# MB_ADC.net
KiCad netlist of a schematic drawn in Altium Designer
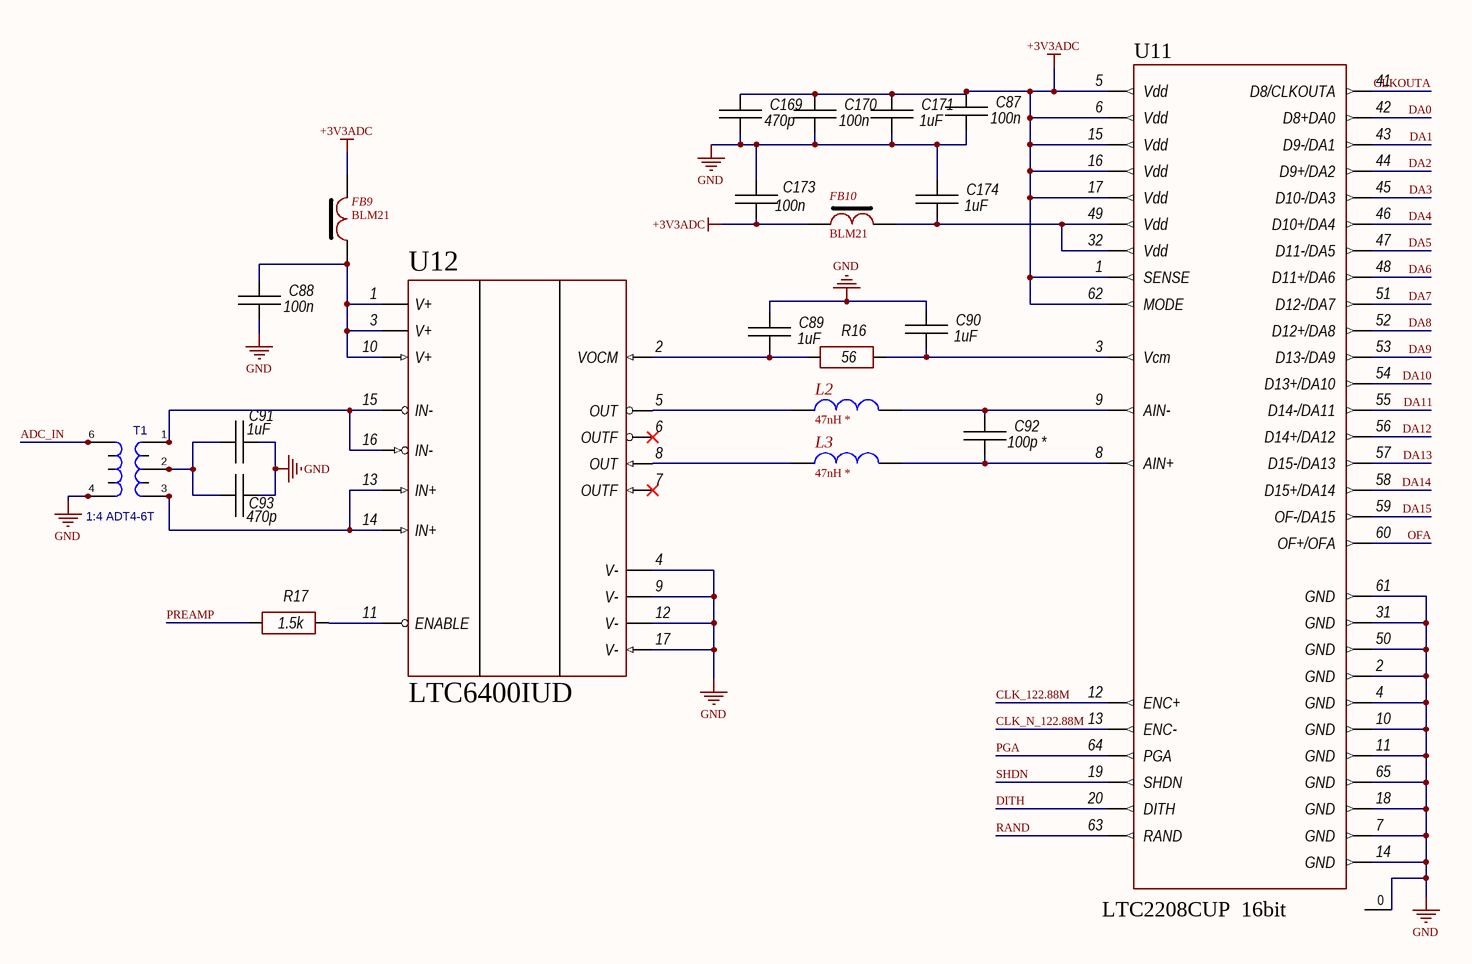
[diagram p0: MB_ADC.SchDoc]

(export (version "E")
  (design (tool "Eeschema 10.0.6"))
  (components
    (comp (ref "C87")
      (value "100n")
      (footprint "standard:CH0805C")
      (libsource (lib "Discrete") (part "Capacitor"))
    )
    (comp (ref "C88")
      (value "100n")
      (footprint "standard:CH0805C")
      (libsource (lib "Discrete") (part "Capacitor"))
    )
    (comp (ref "C89")
      (value "1uF")
      (footprint "standard:CH0805C")
      (libsource (lib "Discrete") (part "Capacitor"))
    )
    (comp (ref "C90")
      (value "1uF")
      (footprint "standard:CH0805C")
      (libsource (lib "Discrete") (part "Capacitor"))
    )
    (comp (ref "C91")
      (value "1uF")
      (footprint "standard:CH0805C")
      (libsource (lib "Discrete") (part "Capacitor"))
    )
    (comp (ref "C92")
      (value "100p *")
      (footprint "standard:CH0805C")
      (libsource (lib "") (part "Capacitor_1"))
    )
    (comp (ref "C93")
      (value "470p")
      (footprint "standard:CH0805C")
      (libsource (lib "Discrete") (part "Capacitor"))
    )
    (comp (ref "C169")
      (value "470p")
      (footprint "standard:CH0805C")
      (libsource (lib "Discrete") (part "Capacitor"))
    )
    (comp (ref "C170")
      (value "100n")
      (footprint "standard:CH0805C")
      (libsource (lib "Discrete") (part "Capacitor"))
    )
    (comp (ref "C171")
      (value "1uF")
      (footprint "standard:CH0805C")
      (libsource (lib "Discrete") (part "Capacitor"))
    )
    (comp (ref "C173")
      (value "100n")
      (footprint "standard:CH0805C")
      (libsource (lib "Discrete") (part "Capacitor"))
    )
    (comp (ref "C174")
      (value "1uF")
      (footprint "standard:CH0805C")
      (libsource (lib "Discrete") (part "Capacitor"))
    )
    (comp (ref "FB9") (value "BLM21") (footprint "CH0805L") (libsource (lib "Discrete") (part "FB-1")))
    (comp (ref "FB10") (value "BLM21") (footprint "CH0805F") (libsource (lib "Discrete") (part "FB-1")))
    (comp (ref "L2") (value "47nH *") (footprint "CH1210L") (libsource (lib "Discrete") (part "Inductor-2")))
    (comp (ref "L3") (value "47nH *") (footprint "CH1210L") (libsource (lib "Discrete") (part "Inductor-2")))
    (comp (ref "R16")
      (value "56")
      (footprint "standard:CH0805R")
      (libsource (lib "Discrete") (part "Resistor"))
    )
    (comp (ref "R17")
      (value "1.5k")
      (footprint "standard:CH0805R")
      (libsource (lib "Discrete") (part "Resistor"))
    )
    (comp (ref "T1")
      (value "1:4 ADT4-6T")
      (footprint "TRANSF_ACORE2")
      (description "Transformer")
      (libsource (lib "MOTHERBOARD_1") (part "TRANSF_ACORE2"))
    )
    (comp (ref "U11")
      (value "LTC2208CUP  16bit")
      (footprint "64-QFN (9x9)")
      (libsource (lib "Digital") (part "LTC2208CUP"))
    )
    (comp (ref "U12")
      (value "LTC6400IUD")
      (footprint "16-QFN 3x3")
      (libsource (lib "Digital") (part "LTC6400IUD"))
    )
  )
  (nets
    (net (code "1") (name "+3V3ADC") (class "Default")
      (node (ref "C169") (pin "1") (pinfunction "1_1") (pintype "power_in"))
      (node (ref "C170") (pin "1") (pinfunction "1_1") (pintype "power_in"))
      (node (ref "C171") (pin "1") (pinfunction "1_1") (pintype "power_in"))
      (node (ref "C173") (pin "2") (pinfunction "2_2") (pintype "power_in"))
      (node (ref "C87") (pin "1") (pinfunction "1_1") (pintype "power_in"))
      (node (ref "FB10") (pin "2") (pinfunction "2_2") (pintype "passive"))
      (node (ref "FB9") (pin "1") (pinfunction "1_1") (pintype "passive"))
      (node (ref "U11") (pin "1") (pinfunction "SENSE_1") (pintype "output"))
      (node (ref "U11") (pin "15") (pinfunction "Vdd_15") (pintype "output"))
      (node (ref "U11") (pin "16") (pinfunction "Vdd_16") (pintype "output"))
      (node (ref "U11") (pin "17") (pinfunction "Vdd_17") (pintype "output"))
      (node (ref "U11") (pin "5") (pinfunction "Vdd_5") (pintype "output"))
      (node (ref "U11") (pin "6") (pinfunction "Vdd_6") (pintype "output"))
      (node (ref "U11") (pin "62") (pinfunction "MODE_62") (pintype "output"))
    )
    (net (code "2") (name "/ADC_IN") (class "Default")
      (node (ref "T1") (pin "10") (pinfunction "0_10") (pintype "passive"))
      (node (ref "T1") (pin "6") (pinfunction "P2_6") (pintype "passive"))
    )
    (net (code "3") (name "/CLKOUTA") (class "Default")
      (node (ref "U11") (pin "41") (pinfunction "D8/CLKOUTA_41") (pintype "output"))
    )
    (net (code "4") (name "/CLK_122.88M") (class "Default")
      (node (ref "U11") (pin "12") (pinfunction "ENC+_12") (pintype "output"))
    )
    (net (code "5") (name "/CLK_N_122.88M") (class "Default")
      (node (ref "U11") (pin "13") (pinfunction "ENC-_13") (pintype "output"))
    )
    (net (code "6") (name "/DA0") (class "Default")
      (node (ref "U11") (pin "42") (pinfunction "D8+DA0_42") (pintype "output"))
    )
    (net (code "7") (name "/DA1") (class "Default")
      (node (ref "U11") (pin "43") (pinfunction "D9-/DA1_43") (pintype "output"))
    )
    (net (code "8") (name "/DA2") (class "Default")
      (node (ref "U11") (pin "44") (pinfunction "D9+/DA2_44") (pintype "output"))
    )
    (net (code "9") (name "/DA3") (class "Default")
      (node (ref "U11") (pin "45") (pinfunction "D10-/DA3_45") (pintype "output"))
    )
    (net (code "10") (name "/DA4") (class "Default")
      (node (ref "U11") (pin "46") (pinfunction "D10+/DA4_46") (pintype "output"))
    )
    (net (code "11") (name "/DA5") (class "Default")
      (node (ref "U11") (pin "47") (pinfunction "D11-/DA5_47") (pintype "output"))
    )
    (net (code "12") (name "/DA6") (class "Default")
      (node (ref "U11") (pin "48") (pinfunction "D11+/DA6_48") (pintype "output"))
    )
    (net (code "13") (name "/DA7") (class "Default")
      (node (ref "U11") (pin "51") (pinfunction "D12-/DA7_51") (pintype "output"))
    )
    (net (code "14") (name "/DA8") (class "Default")
      (node (ref "U11") (pin "52") (pinfunction "D12+/DA8_52") (pintype "output"))
    )
    (net (code "15") (name "/DA9") (class "Default")
      (node (ref "U11") (pin "53") (pinfunction "D13-/DA9_53") (pintype "output"))
    )
    (net (code "16") (name "/DA10") (class "Default")
      (node (ref "U11") (pin "54") (pinfunction "D13+/DA10_54") (pintype "output"))
    )
    (net (code "17") (name "/DA11") (class "Default")
      (node (ref "U11") (pin "55") (pinfunction "D14-/DA11_55") (pintype "output"))
    )
    (net (code "18") (name "/DA12") (class "Default")
      (node (ref "U11") (pin "56") (pinfunction "D14+/DA12_56") (pintype "output"))
    )
    (net (code "19") (name "/DA13") (class "Default")
      (node (ref "U11") (pin "57") (pinfunction "D15-/DA13_57") (pintype "output"))
    )
    (net (code "20") (name "/DA14") (class "Default")
      (node (ref "U11") (pin "58") (pinfunction "D15+/DA14_58") (pintype "output"))
    )
    (net (code "21") (name "/DA15") (class "Default")
      (node (ref "U11") (pin "59") (pinfunction "OF-/DA15_59") (pintype "output"))
    )
    (net (code "22") (name "/DITH") (class "Default")
      (node (ref "U11") (pin "20") (pinfunction "DITH_20") (pintype "output"))
    )
    (net (code "23") (name "/OFA") (class "Default")
      (node (ref "U11") (pin "60") (pinfunction "OF+/OFA_60") (pintype "output"))
    )
    (net (code "24") (name "/PGA") (class "Default")
      (node (ref "U11") (pin "64") (pinfunction "PGA_64") (pintype "output"))
    )
    (net (code "25") (name "/PREAMP") (class "Default")
      (node (ref "R17") (pin "2") (pinfunction "2_2") (pintype "passive"))
    )
    (net (code "26") (name "/RAND") (class "Default")
      (node (ref "U11") (pin "63") (pinfunction "RAND_63") (pintype "output"))
    )
    (net (code "27") (name "/SHDN") (class "Default")
      (node (ref "U11") (pin "19") (pinfunction "SHDN_19") (pintype "output"))
    )
    (net (code "28") (name "GND") (class "Default")
      (node (ref "C169") (pin "2") (pinfunction "2_2") (pintype "power_in"))
      (node (ref "C170") (pin "2") (pinfunction "2_2") (pintype "power_in"))
      (node (ref "C171") (pin "2") (pinfunction "2_2") (pintype "power_in"))
      (node (ref "C173") (pin "1") (pinfunction "1_1") (pintype "power_in"))
      (node (ref "C174") (pin "1") (pinfunction "1_1") (pintype "power_in"))
      (node (ref "C87") (pin "2") (pinfunction "2_2") (pintype "power_in"))
      (node (ref "C88") (pin "2") (pinfunction "2_2") (pintype "power_in"))
      (node (ref "C89") (pin "1") (pinfunction "1_1") (pintype "power_in"))
      (node (ref "C90") (pin "1") (pinfunction "1_1") (pintype "power_in"))
      (node (ref "C91") (pin "2") (pinfunction "2_2") (pintype "power_in"))
      (node (ref "C93") (pin "2") (pinfunction "2_2") (pintype "power_in"))
      (node (ref "T1") (pin "11") (pinfunction "0_11") (pintype "passive"))
      (node (ref "T1") (pin "4") (pinfunction "P1_4") (pintype "passive"))
      (node (ref "U11") (pin "0") (pintype "passive"))
      (node (ref "U11") (pin "10") (pinfunction "GND_10") (pintype "output"))
      (node (ref "U11") (pin "11") (pinfunction "GND_11") (pintype "output"))
      (node (ref "U11") (pin "14") (pinfunction "GND_14") (pintype "output"))
      (node (ref "U11") (pin "18") (pinfunction "GND_18") (pintype "output"))
      (node (ref "U11") (pin "2") (pinfunction "GND_2") (pintype "output"))
      (node (ref "U11") (pin "31") (pinfunction "GND_31") (pintype "output"))
      (node (ref "U11") (pin "4") (pinfunction "GND_4") (pintype "output"))
      (node (ref "U11") (pin "50") (pinfunction "GND_50") (pintype "output"))
      (node (ref "U11") (pin "61") (pinfunction "GND_61") (pintype "output"))
      (node (ref "U11") (pin "65") (pinfunction "GND_65") (pintype "output"))
      (node (ref "U11") (pin "7") (pinfunction "GND_7") (pintype "output"))
      (node (ref "U12") (pin "12") (pinfunction "V-_12") (pintype "power_in"))
      (node (ref "U12") (pin "17") (pinfunction "V-_17") (pintype "input"))
      (node (ref "U12") (pin "4") (pinfunction "V-_4") (pintype "passive"))
      (node (ref "U12") (pin "9") (pinfunction "V-_9") (pintype "power_in"))
    )
    (net (code "29") (name "Net-(C88-Pad1)") (class "Default")
      (node (ref "C88") (pin "1") (pinfunction "1_1") (pintype "power_in"))
      (node (ref "FB9") (pin "2") (pinfunction "2_2") (pintype "passive"))
      (node (ref "U12") (pin "1") (pinfunction "V+_1") (pintype "passive"))
      (node (ref "U12") (pin "10") (pinfunction "V+_10") (pintype "input"))
      (node (ref "U12") (pin "3") (pinfunction "V+_3") (pintype "power_in"))
    )
    (net (code "30") (name "Net-(C174-Pad2)") (class "Default")
      (node (ref "C174") (pin "2") (pinfunction "2_2") (pintype "power_in"))
      (node (ref "FB10") (pin "1") (pinfunction "1_1") (pintype "passive"))
      (node (ref "U11") (pin "32") (pinfunction "Vdd_32") (pintype "output"))
      (node (ref "U11") (pin "49") (pinfunction "Vdd_49") (pintype "output"))
    )
    (net (code "31") (name "Net-(L2-Pad2)") (class "Default")
      (node (ref "L2") (pin "2") (pinfunction "2_2") (pintype "passive"))
      (node (ref "U12") (pin "5") (pinfunction "OUT_5") (pintype "passive"))
    )
    (net (code "32") (name "Net-(L3-Pad2)") (class "Default")
      (node (ref "L3") (pin "2") (pinfunction "2_2") (pintype "passive"))
      (node (ref "U12") (pin "8") (pinfunction "OUT_8") (pintype "input"))
    )
    (net (code "33") (name "Net-(T1-S1)") (class "Default")
      (node (ref "T1") (pin "3") (pinfunction "S1_3") (pintype "passive"))
      (node (ref "T1") (pin "9") (pinfunction "0_9") (pintype "passive"))
      (node (ref "U12") (pin "13") (pinfunction "IN+_13") (pintype "input"))
      (node (ref "U12") (pin "14") (pinfunction "IN+_14") (pintype "input"))
    )
    (net (code "34") (name "Net-(T1-S2)") (class "Default")
      (node (ref "C91") (pin "1") (pinfunction "1_1") (pintype "power_in"))
      (node (ref "C93") (pin "1") (pinfunction "1_1") (pintype "power_in"))
      (node (ref "T1") (pin "2") (pinfunction "S2_2") (pintype "passive"))
      (node (ref "T1") (pin "8") (pinfunction "0_8") (pintype "passive"))
    )
    (net (code "35") (name "Net-(T1-S3)") (class "Default")
      (node (ref "T1") (pin "1") (pinfunction "S3_1") (pintype "passive"))
      (node (ref "T1") (pin "7") (pinfunction "0_7") (pintype "passive"))
      (node (ref "U12") (pin "15") (pinfunction "IN-_15") (pintype "passive"))
      (node (ref "U12") (pin "16") (pinfunction "IN-_16") (pintype "input"))
    )
    (net (code "36") (name "Net-(U11-AIN+)") (class "Default")
      (node (ref "C92") (pin "2") (pinfunction "2_2") (pintype "power_in"))
      (node (ref "L3") (pin "1") (pinfunction "1_1") (pintype "passive"))
      (node (ref "U11") (pin "8") (pinfunction "AIN+_8") (pintype "output"))
    )
    (net (code "37") (name "Net-(U11-AIN-)") (class "Default")
      (node (ref "C92") (pin "1") (pinfunction "1_1") (pintype "power_in"))
      (node (ref "L2") (pin "1") (pinfunction "1_1") (pintype "passive"))
      (node (ref "U11") (pin "9") (pinfunction "AIN-_9") (pintype "output"))
    )
    (net (code "38") (name "Net-(U11-Vcm)") (class "Default")
      (node (ref "C90") (pin "2") (pinfunction "2_2") (pintype "power_in"))
      (node (ref "R16") (pin "1") (pinfunction "1_1") (pintype "passive"))
      (node (ref "U11") (pin "3") (pinfunction "Vcm_3") (pintype "output"))
    )
    (net (code "39") (name "Net-(U12-ENABLE)") (class "Default")
      (node (ref "R17") (pin "1") (pinfunction "1_1") (pintype "passive"))
      (node (ref "U12") (pin "11") (pinfunction "ENABLE_11") (pintype "passive"))
    )
    (net (code "40") (name "Net-(U12-VOCM)") (class "Default")
      (node (ref "C89") (pin "2") (pinfunction "2_2") (pintype "power_in"))
      (node (ref "R16") (pin "2") (pinfunction "2_2") (pintype "passive"))
      (node (ref "U12") (pin "2") (pinfunction "VOCM_2") (pintype "input"))
    )
    (net (code "41") (name "unconnected-(U12-OUTF-Pad6)") (class "Default")
      (node (ref "U12") (pin "6") (pinfunction "OUTF_6") (pintype "passive+no_connect"))
    )
    (net (code "42") (name "unconnected-(U12-OUTF-Pad7)") (class "Default")
      (node (ref "U12") (pin "7") (pinfunction "OUTF_7") (pintype "input+no_connect"))
    )
  )
)
